# 04A-015.net
KiCad netlist of a schematic drawn in EAGLE
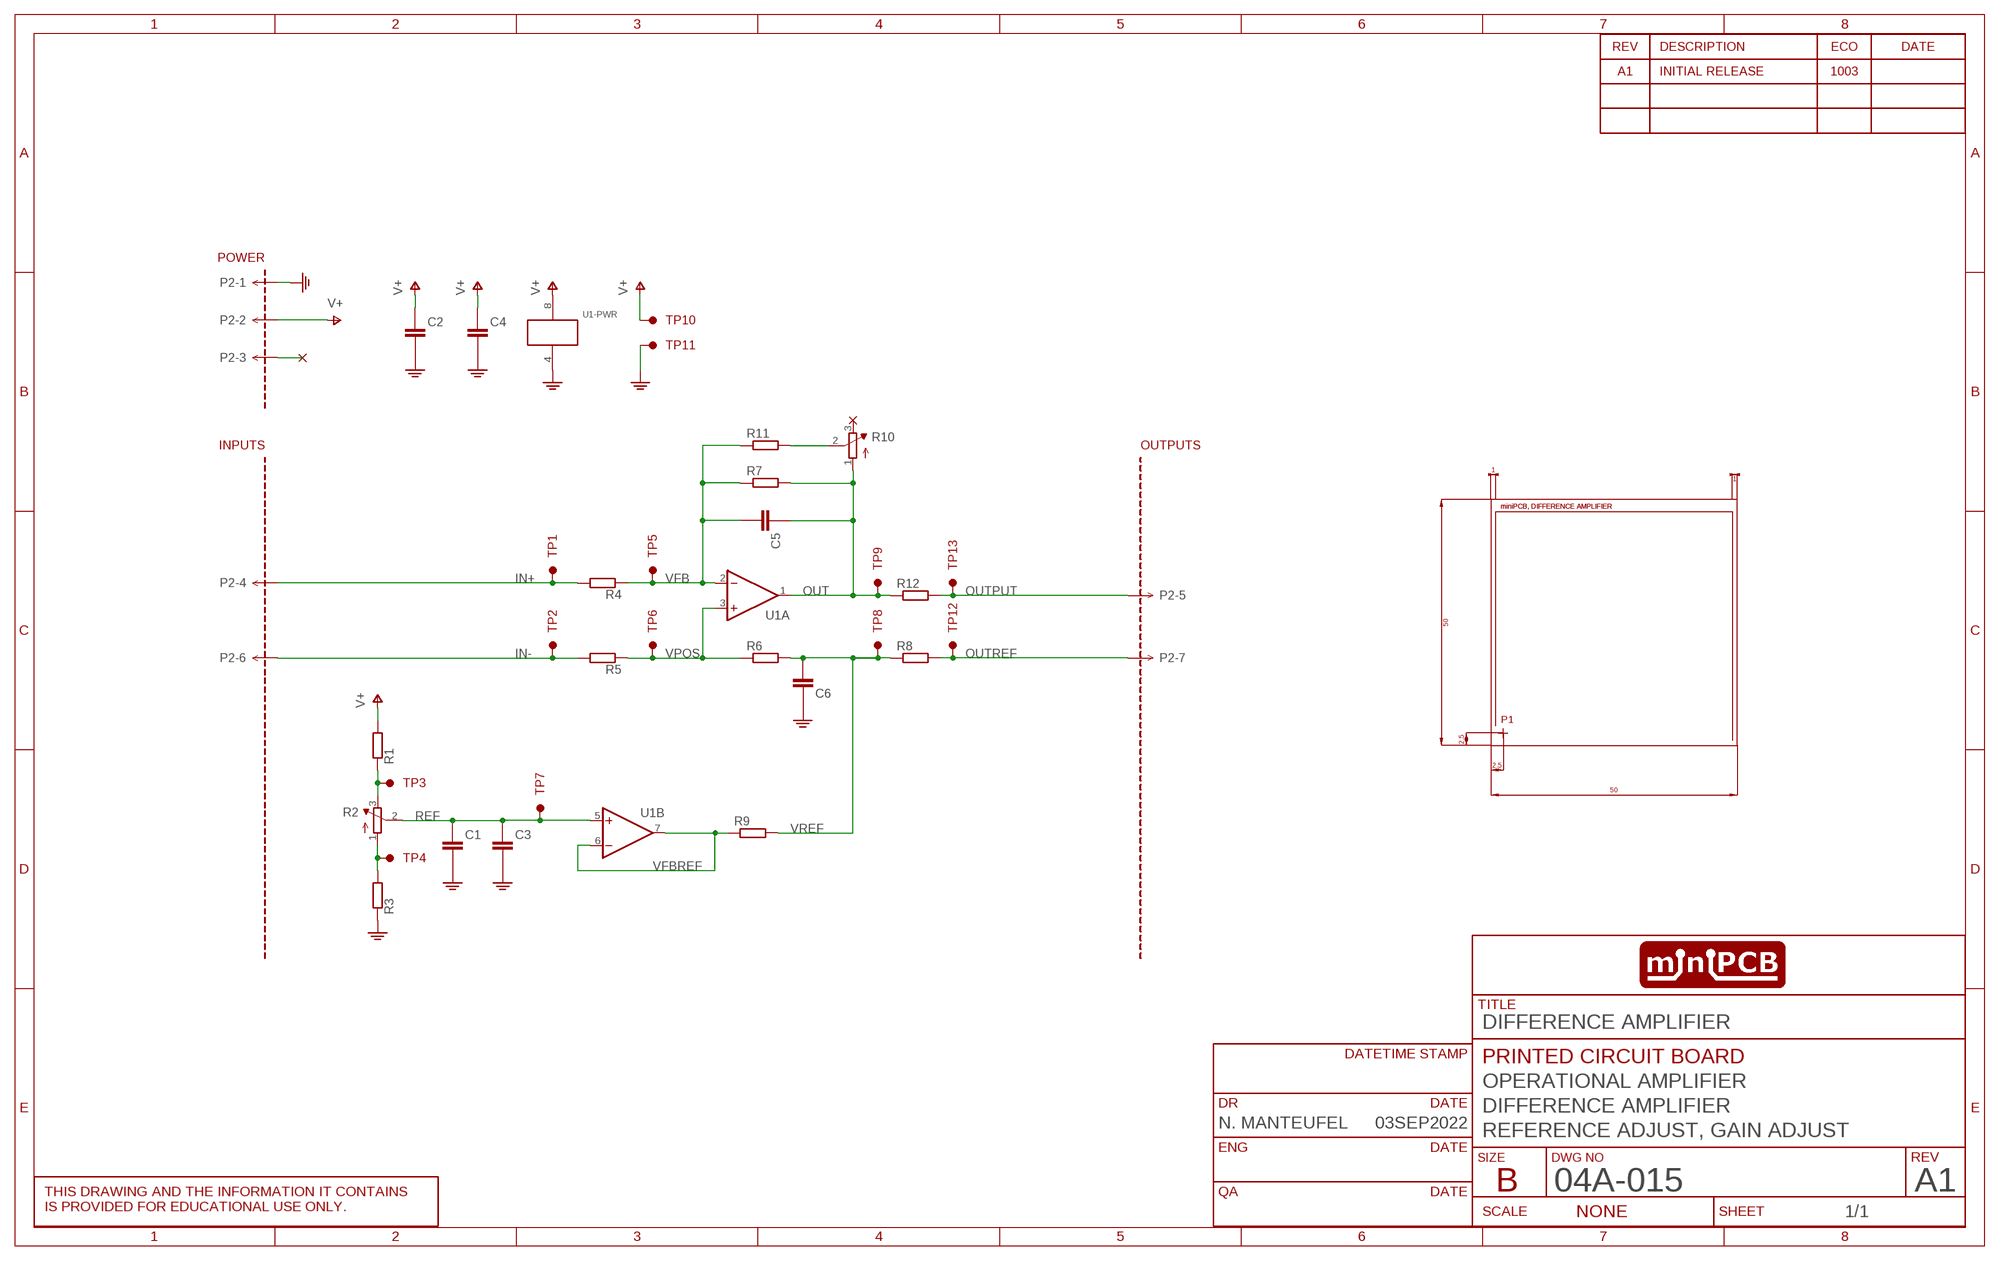
[diagram p0: schematic, sheet 1]

(export (version "E")
  (design (tool "Eeschema 10.0.6"))
  (components
    (comp (ref "C1")
      (value "CAPACITORTHD")
      (footprint "eagle-import:C050-024X044")
      (libsource (lib "eagle-import") (part "CAPACITORTHD"))
    )
    (comp (ref "C2")
      (value "CAPACITORTHD")
      (footprint "eagle-import:C050-024X044")
      (libsource (lib "eagle-import") (part "CAPACITORTHD"))
    )
    (comp (ref "C3")
      (value "CAPACITOR_10")
      (footprint "eagle-import:C5MM")
      (libsource (lib "eagle-import") (part "CAPACITOR_10"))
    )
    (comp (ref "C4")
      (value "CAPACITOR_10")
      (footprint "eagle-import:C5MM")
      (libsource (lib "eagle-import") (part "CAPACITOR_10"))
    )
    (comp (ref "C5")
      (value "CAPACITORTHD")
      (footprint "eagle-import:C050-024X044")
      (libsource (lib "eagle-import") (part "CAPACITORTHD"))
    )
    (comp (ref "C6")
      (value "CAPACITORTHD")
      (footprint "eagle-import:C050-024X044")
      (libsource (lib "eagle-import") (part "CAPACITORTHD"))
    )
    (comp (ref "P2")
      (value "MINIPCB_7P")
      (footprint "eagle-import:PINS_1X7")
      (libsource (lib "eagle-import") (part "MINIPCB_7P"))
    )
    (comp (ref "R1")
      (value "RESISTOR10MM")
      (footprint "eagle-import:0207_10")
      (libsource (lib "eagle-import") (part "RESISTOR10MM"))
    )
    (comp (ref "R2")
      (value "TRIMPOT0.100THD")
      (footprint "eagle-import:TRIM_0100")
      (libsource (lib "eagle-import") (part "TRIMPOT0.100THD"))
    )
    (comp (ref "R3")
      (value "RESISTOR10MM")
      (footprint "eagle-import:0207_10")
      (libsource (lib "eagle-import") (part "RESISTOR10MM"))
    )
    (comp (ref "R4")
      (value "RESISTOR10MM")
      (footprint "eagle-import:0207_10")
      (libsource (lib "eagle-import") (part "RESISTOR10MM"))
    )
    (comp (ref "R5")
      (value "RESISTOR10MM")
      (footprint "eagle-import:0207_10")
      (libsource (lib "eagle-import") (part "RESISTOR10MM"))
    )
    (comp (ref "R6")
      (value "RESISTOR10MM")
      (footprint "eagle-import:0207_10")
      (libsource (lib "eagle-import") (part "RESISTOR10MM"))
    )
    (comp (ref "R7")
      (value "RESISTOR10MM")
      (footprint "eagle-import:0207_10")
      (libsource (lib "eagle-import") (part "RESISTOR10MM"))
    )
    (comp (ref "R8")
      (value "RESISTOR10MM")
      (footprint "eagle-import:0207_10")
      (libsource (lib "eagle-import") (part "RESISTOR10MM"))
    )
    (comp (ref "R9")
      (value "RESISTOR10MM")
      (footprint "eagle-import:0207_10")
      (libsource (lib "eagle-import") (part "RESISTOR10MM"))
    )
    (comp (ref "R10")
      (value "TRIMPOT0.100THD")
      (footprint "eagle-import:TRIM_0100")
      (libsource (lib "eagle-import") (part "TRIMPOT0.100THD"))
    )
    (comp (ref "R11")
      (value "RESISTOR10MM")
      (footprint "eagle-import:0207_10")
      (libsource (lib "eagle-import") (part "RESISTOR10MM"))
    )
    (comp (ref "R12")
      (value "RESISTOR10MM")
      (footprint "eagle-import:0207_10")
      (libsource (lib "eagle-import") (part "RESISTOR10MM"))
    )
    (comp (ref "TP1")
      (value "TESTPOINTKE5000-SMTEXT")
      (footprint "eagle-import:PINS_1_TESTPOINT_KE5000_NOTEXT")
      (libsource (lib "eagle-import") (part "TESTPOINTKE5000-SMTEXT"))
    )
    (comp (ref "TP2")
      (value "TESTPOINTKE5000-SMTEXT")
      (footprint "eagle-import:PINS_1_TESTPOINT_KE5000_NOTEXT")
      (libsource (lib "eagle-import") (part "TESTPOINTKE5000-SMTEXT"))
    )
    (comp (ref "TP3")
      (value "TESTPOINTKE5000-SMTEXT")
      (footprint "eagle-import:PINS_1_TESTPOINT_KE5000_NOTEXT")
      (libsource (lib "eagle-import") (part "TESTPOINTKE5000-SMTEXT"))
    )
    (comp (ref "TP4")
      (value "TESTPOINTKE5000-SMTEXT")
      (footprint "eagle-import:PINS_1_TESTPOINT_KE5000_NOTEXT")
      (libsource (lib "eagle-import") (part "TESTPOINTKE5000-SMTEXT"))
    )
    (comp (ref "TP5")
      (value "TESTPOINTKE5000-SMTEXT")
      (footprint "eagle-import:PINS_1_TESTPOINT_KE5000_NOTEXT")
      (libsource (lib "eagle-import") (part "TESTPOINTKE5000-SMTEXT"))
    )
    (comp (ref "TP6")
      (value "TESTPOINTKE5000-SMTEXT")
      (footprint "eagle-import:PINS_1_TESTPOINT_KE5000_NOTEXT")
      (libsource (lib "eagle-import") (part "TESTPOINTKE5000-SMTEXT"))
    )
    (comp (ref "TP7")
      (value "TESTPOINTKE5000-SMTEXT")
      (footprint "eagle-import:PINS_1_TESTPOINT_KE5000_NOTEXT")
      (libsource (lib "eagle-import") (part "TESTPOINTKE5000-SMTEXT"))
    )
    (comp (ref "TP8")
      (value "TESTPOINTKE5000-SMTEXT")
      (footprint "eagle-import:PINS_1_TESTPOINT_KE5000_NOTEXT")
      (libsource (lib "eagle-import") (part "TESTPOINTKE5000-SMTEXT"))
    )
    (comp (ref "TP9")
      (value "TESTPOINTKE5000-SMTEXT")
      (footprint "eagle-import:PINS_1_TESTPOINT_KE5000_NOTEXT")
      (libsource (lib "eagle-import") (part "TESTPOINTKE5000-SMTEXT"))
    )
    (comp (ref "TP10")
      (value "TESTPOINTKE5000-SMTEXT")
      (footprint "eagle-import:PINS_1_TESTPOINT_KE5000_NOTEXT")
      (libsource (lib "eagle-import") (part "TESTPOINTKE5000-SMTEXT"))
    )
    (comp (ref "TP11")
      (value "TESTPOINTKE5000-SMTEXT")
      (footprint "eagle-import:PINS_1_TESTPOINT_KE5000_NOTEXT")
      (libsource (lib "eagle-import") (part "TESTPOINTKE5000-SMTEXT"))
    )
    (comp (ref "TP12")
      (value "TESTPOINTKE5000-SMTEXT")
      (footprint "eagle-import:PINS_1_TESTPOINT_KE5000_NOTEXT")
      (libsource (lib "eagle-import") (part "TESTPOINTKE5000-SMTEXT"))
    )
    (comp (ref "TP13")
      (value "TESTPOINTKE5000-SMTEXT")
      (footprint "eagle-import:PINS_1_TESTPOINT_KE5000_NOTEXT")
      (libsource (lib "eagle-import") (part "TESTPOINTKE5000-SMTEXT"))
    )
    (comp (ref "U$1")
      (value "CLASSIC-50")
      (footprint "eagle-import:PCB50")
      (fields
        (field (name "PART_NUMBER") "000-000")
        (field (name "PART_NUMBER_1") "04A-015")
        (field (name "TITLE") "miniPCB, DIFFERENCE AMPLIFIER")
      )
      (libsource (lib "eagle-import") (part "CLASSIC-50"))
    )
    (comp (ref "U1")
      (value "OPAMP_DUALTHD")
      (footprint "eagle-import:DIL08")
      (libsource (lib "eagle-import") (part "OPAMP_DUALTHD"))
    )
  )
  (nets
    (net (code "1") (name "/IN+") (class "Default")
      (node (ref "P2") (pin "4") (pinfunction "1_4") (pintype "bidirectional"))
      (node (ref "R4") (pin "2") (pinfunction "2_2") (pintype "passive"))
      (node (ref "TP1") (pin "1") (pinfunction "1_1") (pintype "bidirectional"))
    )
    (net (code "2") (name "/IN-") (class "Default")
      (node (ref "P2") (pin "6") (pinfunction "1_6") (pintype "bidirectional"))
      (node (ref "R5") (pin "2") (pinfunction "2_2") (pintype "passive"))
      (node (ref "TP2") (pin "1") (pinfunction "1_1") (pintype "bidirectional"))
    )
    (net (code "3") (name "/OUT") (class "Default")
      (node (ref "C5") (pin "1") (pinfunction "+_1") (pintype "passive"))
      (node (ref "R10") (pin "1") (pinfunction "A_1") (pintype "passive"))
      (node (ref "R12") (pin "1") (pinfunction "1_1") (pintype "passive"))
      (node (ref "R7") (pin "2") (pinfunction "2_2") (pintype "passive"))
      (node (ref "TP9") (pin "1") (pinfunction "1_1") (pintype "bidirectional"))
      (node (ref "U1") (pin "1") (pinfunction "OUT_1") (pintype "output"))
    )
    (net (code "4") (name "/OUTPUT") (class "Default")
      (node (ref "P2") (pin "5") (pinfunction "1_5") (pintype "bidirectional"))
      (node (ref "R12") (pin "2") (pinfunction "2_2") (pintype "passive"))
      (node (ref "TP13") (pin "1") (pinfunction "1_1") (pintype "bidirectional"))
    )
    (net (code "5") (name "/OUTREF") (class "Default")
      (node (ref "P2") (pin "7") (pinfunction "1_7") (pintype "bidirectional"))
      (node (ref "R8") (pin "2") (pinfunction "2_2") (pintype "passive"))
      (node (ref "TP12") (pin "1") (pinfunction "1_1") (pintype "bidirectional"))
    )
    (net (code "6") (name "/REF") (class "Default")
      (node (ref "C1") (pin "1") (pinfunction "+_1") (pintype "passive"))
      (node (ref "C3") (pin "+") (pinfunction "+_+") (pintype "passive"))
      (node (ref "R2") (pin "2") (pinfunction "S_2") (pintype "passive"))
      (node (ref "TP7") (pin "1") (pinfunction "1_1") (pintype "bidirectional"))
      (node (ref "U1") (pin "5") (pinfunction "+IN_5") (pintype "input"))
    )
    (net (code "7") (name "/VFB") (class "Default")
      (node (ref "C5") (pin "2") (pinfunction "-_2") (pintype "passive"))
      (node (ref "R11") (pin "1") (pinfunction "1_1") (pintype "passive"))
      (node (ref "R4") (pin "1") (pinfunction "1_1") (pintype "passive"))
      (node (ref "R7") (pin "1") (pinfunction "1_1") (pintype "passive"))
      (node (ref "TP5") (pin "1") (pinfunction "1_1") (pintype "bidirectional"))
      (node (ref "U1") (pin "2") (pinfunction "-IN_2") (pintype "input"))
    )
    (net (code "8") (name "/VFBREF") (class "Default")
      (node (ref "R9") (pin "1") (pinfunction "1_1") (pintype "passive"))
      (node (ref "U1") (pin "6") (pinfunction "-IN_6") (pintype "input"))
      (node (ref "U1") (pin "7") (pinfunction "OUT_7") (pintype "output"))
    )
    (net (code "9") (name "/VPOS") (class "Default")
      (node (ref "R5") (pin "1") (pinfunction "1_1") (pintype "passive"))
      (node (ref "R6") (pin "1") (pinfunction "1_1") (pintype "passive"))
      (node (ref "TP6") (pin "1") (pinfunction "1_1") (pintype "bidirectional"))
      (node (ref "U1") (pin "3") (pinfunction "+IN_3") (pintype "input"))
    )
    (net (code "10") (name "/VREF") (class "Default")
      (node (ref "C6") (pin "2") (pinfunction "-_2") (pintype "passive"))
      (node (ref "R6") (pin "2") (pinfunction "2_2") (pintype "passive"))
      (node (ref "R8") (pin "1") (pinfunction "1_1") (pintype "passive"))
      (node (ref "R9") (pin "2") (pinfunction "2_2") (pintype "passive"))
      (node (ref "TP8") (pin "1") (pinfunction "1_1") (pintype "bidirectional"))
    )
    (net (code "11") (name "GND") (class "Default")
      (node (ref "C1") (pin "2") (pinfunction "-_2") (pintype "passive"))
      (node (ref "C2") (pin "2") (pinfunction "-_2") (pintype "passive"))
      (node (ref "C3") (pin "-") (pinfunction "-_-") (pintype "passive"))
      (node (ref "C4") (pin "-") (pinfunction "-_-") (pintype "passive"))
      (node (ref "C6") (pin "1") (pinfunction "+_1") (pintype "passive"))
      (node (ref "P2") (pin "1") (pinfunction "1_1") (pintype "bidirectional"))
      (node (ref "R3") (pin "1") (pinfunction "1_1") (pintype "passive"))
      (node (ref "TP11") (pin "1") (pinfunction "1_1") (pintype "bidirectional"))
      (node (ref "U1") (pin "4") (pinfunction "V-_4") (pintype "power_in"))
    )
    (net (code "12") (name "Net-(R2-A)") (class "Default")
      (node (ref "R2") (pin "1") (pinfunction "A_1") (pintype "passive"))
      (node (ref "R3") (pin "2") (pinfunction "2_2") (pintype "passive"))
      (node (ref "TP4") (pin "1") (pinfunction "1_1") (pintype "bidirectional"))
    )
    (net (code "13") (name "Net-(R2-E)") (class "Default")
      (node (ref "R1") (pin "1") (pinfunction "1_1") (pintype "passive"))
      (node (ref "R2") (pin "3") (pinfunction "E_3") (pintype "passive"))
      (node (ref "TP3") (pin "1") (pinfunction "1_1") (pintype "bidirectional"))
    )
    (net (code "14") (name "Net-(R10-S)") (class "Default")
      (node (ref "R10") (pin "2") (pinfunction "S_2") (pintype "passive"))
      (node (ref "R11") (pin "2") (pinfunction "2_2") (pintype "passive"))
    )
    (net (code "15") (name "V+") (class "Default")
      (node (ref "C2") (pin "1") (pinfunction "+_1") (pintype "passive"))
      (node (ref "C4") (pin "+") (pinfunction "+_+") (pintype "passive"))
      (node (ref "P2") (pin "2") (pinfunction "1_2") (pintype "bidirectional"))
      (node (ref "R1") (pin "2") (pinfunction "2_2") (pintype "passive"))
      (node (ref "TP10") (pin "1") (pinfunction "1_1") (pintype "bidirectional"))
      (node (ref "U1") (pin "8") (pinfunction "V+_8") (pintype "power_in"))
    )
    (net (code "16") (name "unconnected-(P2C-1-Pad3)") (class "Default")
      (node (ref "P2") (pin "3") (pinfunction "1_3") (pintype "bidirectional"))
    )
    (net (code "17") (name "unconnected-(R10-E-Pad3)") (class "Default")
      (node (ref "R10") (pin "3") (pinfunction "E_3") (pintype "passive"))
    )
  )
)
